# NAND-7S.net
KiCad netlist of a schematic drawn in EasyEDA Pro
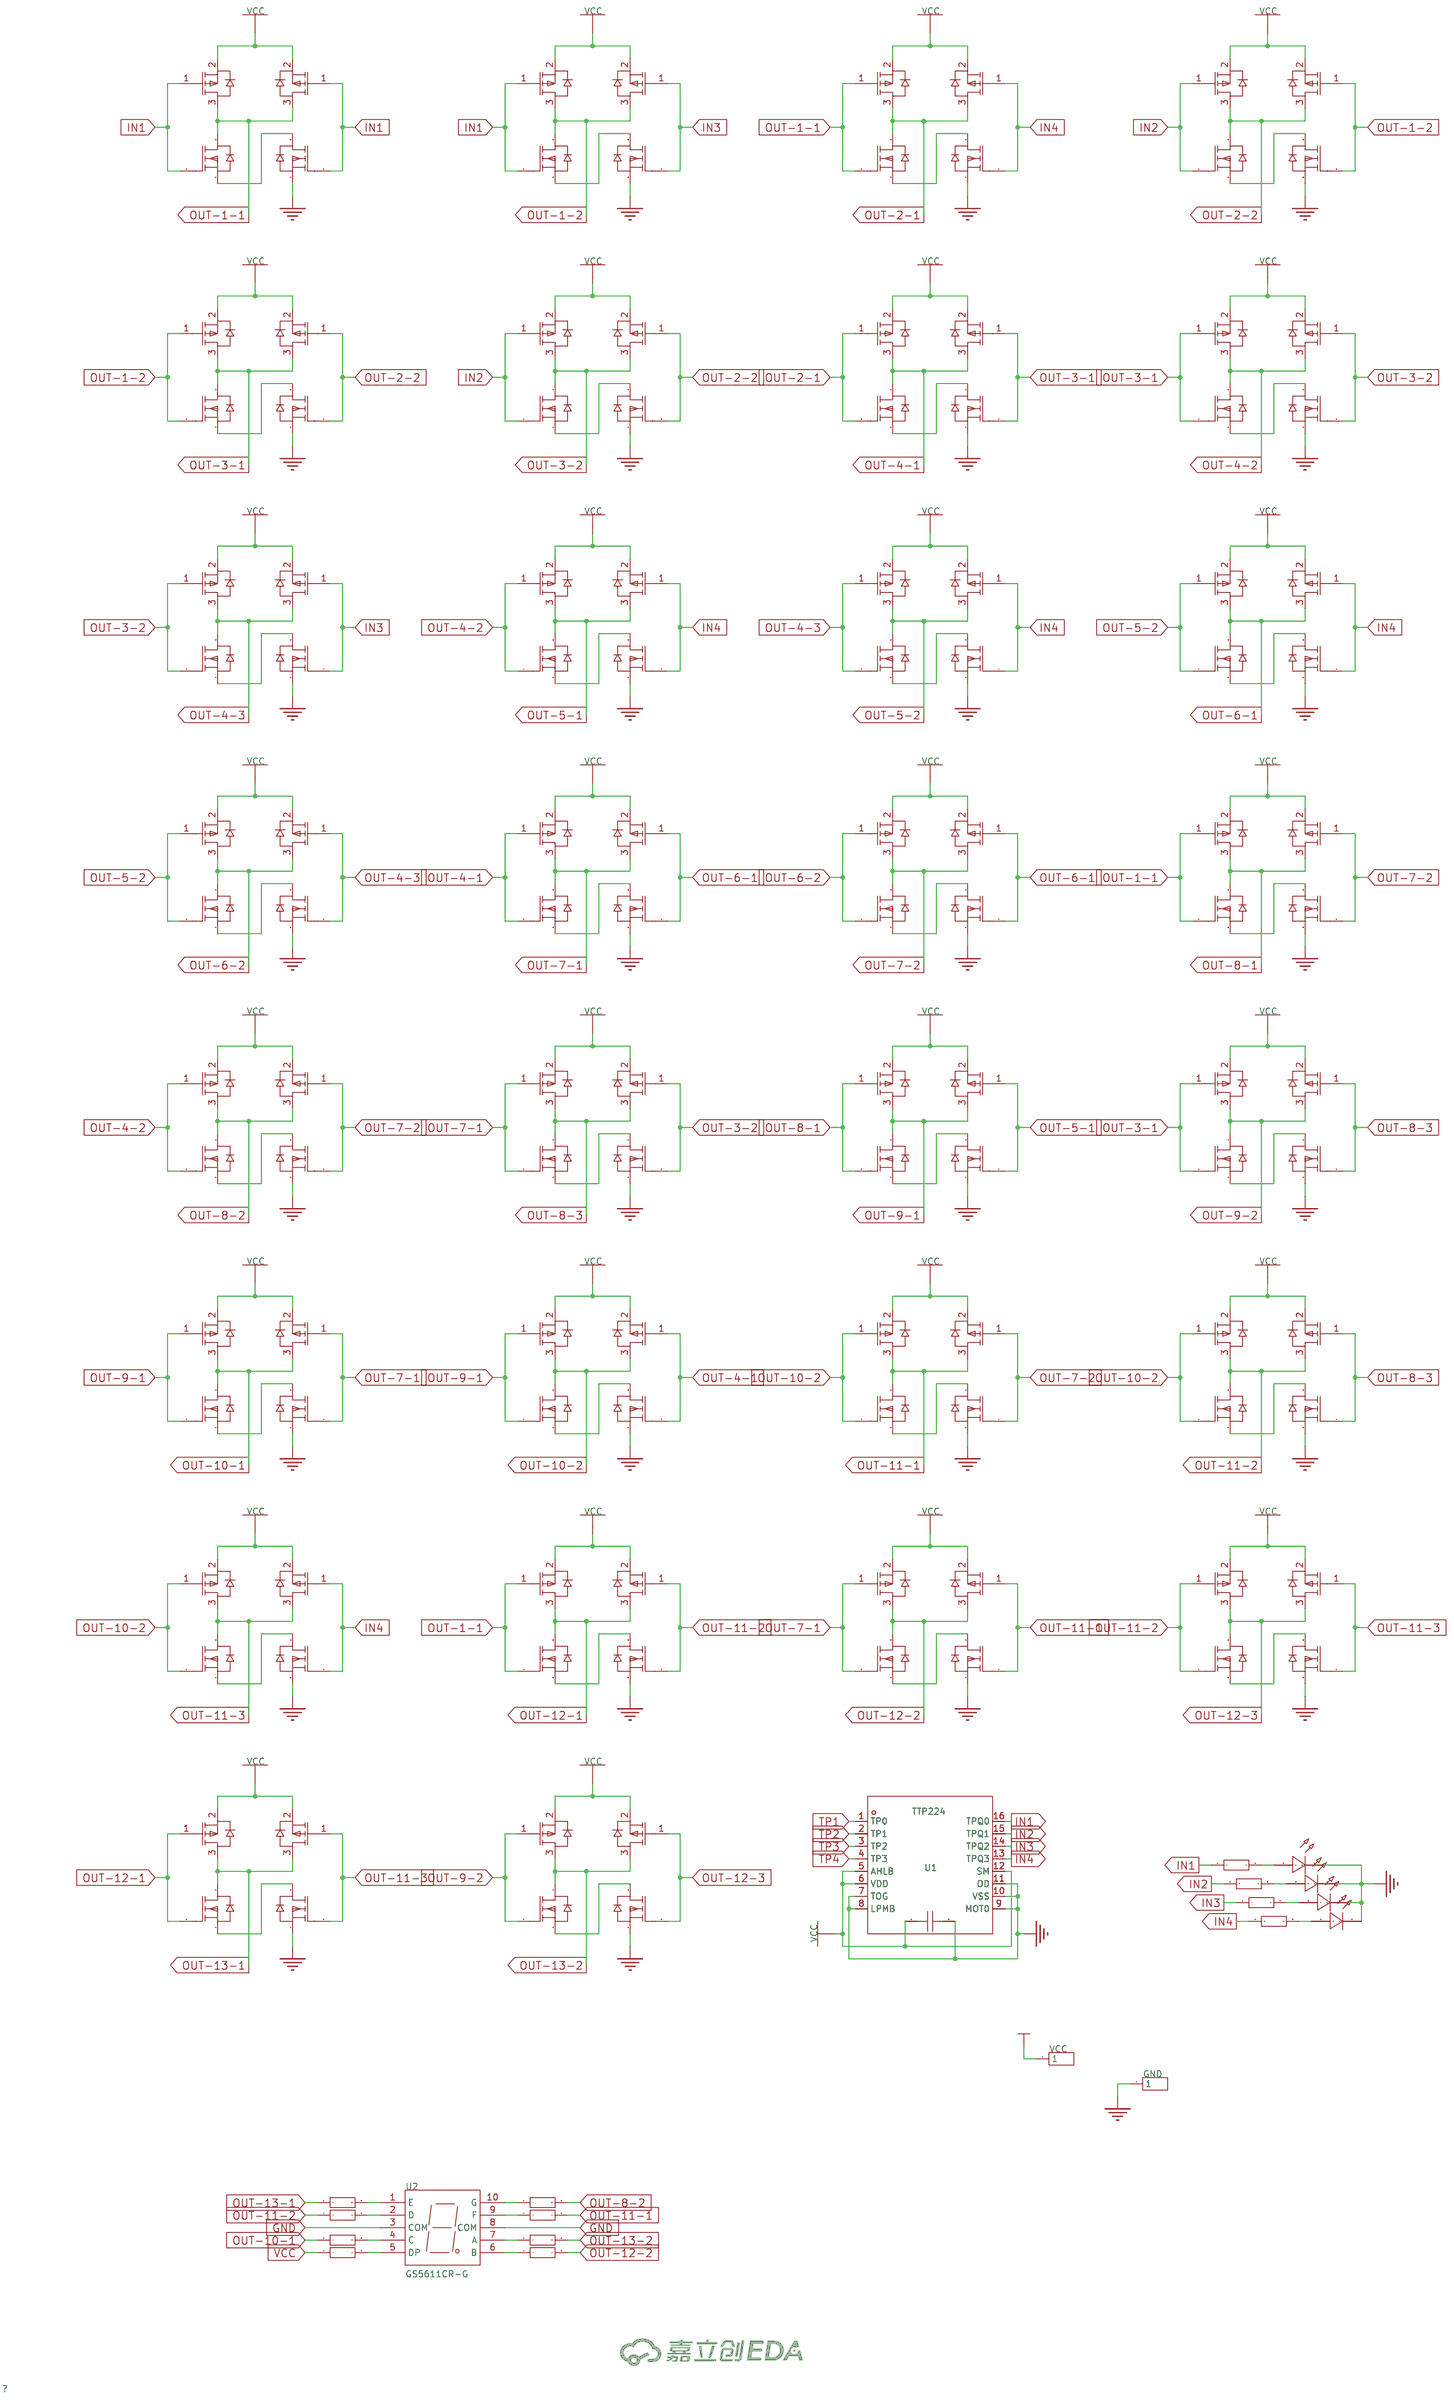
[diagram p0: schematic sheet]

(export (version "E")
  (design (tool "Eeschema 10.0.6"))
  (components
    (comp (ref "C1")
      (value "100nF")
      (footprint "easyedapro:C0603")
      (libsource (lib "easyedapro") (part "Capacitance"))
    )
    (comp (ref "GND")
      (value "GND")
      (footprint "easyedapro:HDR-TH_1P-V-M_XKB_X4611WV-01I-C28D40")
      (libsource (lib "easyedapro") (part "HDR_1x1"))
    )
    (comp (ref "LED1")
      (value "~")
      (footprint "easyedapro:LED_0603")
      (libsource (lib "easyedapro") (part "LED_R"))
    )
    (comp (ref "LED2")
      (value "~")
      (footprint "easyedapro:LED_0603")
      (libsource (lib "easyedapro") (part "LED_R"))
    )
    (comp (ref "LED3")
      (value "~")
      (footprint "easyedapro:LED_0603")
      (libsource (lib "easyedapro") (part "LED_R"))
    )
    (comp (ref "LED4")
      (value "~")
      (footprint "easyedapro:LED_0603")
      (libsource (lib "easyedapro") (part "LED_R"))
    )
    (comp (ref "N1-1")
      (value "CJ2304")
      (footprint "easyedapro:SOT-23_L2.9-W1.3-P1.90-LS2.4-BR")
      (fields (field (name "Manufacturer") "CJ（江苏长电/长晶）"))
      (libsource (lib "easyedapro") (part "2N7002LT1G"))
    )
    (comp (ref "N1-2")
      (value "CJ2304")
      (footprint "easyedapro:SOT-23_L2.9-W1.3-P1.90-LS2.4-BR")
      (fields (field (name "Manufacturer") "CJ（江苏长电/长晶）"))
      (libsource (lib "easyedapro") (part "2N7002LT1G"))
    )
    (comp (ref "N2-1")
      (value "CJ2304")
      (footprint "easyedapro:SOT-23_L2.9-W1.3-P1.90-LS2.4-BR")
      (fields (field (name "Manufacturer") "CJ（江苏长电/长晶）"))
      (libsource (lib "easyedapro") (part "2N7002LT1G"))
    )
    (comp (ref "N2-2")
      (value "CJ2304")
      (footprint "easyedapro:SOT-23_L2.9-W1.3-P1.90-LS2.4-BR")
      (fields (field (name "Manufacturer") "CJ（江苏长电/长晶）"))
      (libsource (lib "easyedapro") (part "2N7002LT1G"))
    )
    (comp (ref "N3-1")
      (value "CJ2304")
      (footprint "easyedapro:SOT-23_L2.9-W1.3-P1.90-LS2.4-BR")
      (fields (field (name "Manufacturer") "CJ（江苏长电/长晶）"))
      (libsource (lib "easyedapro") (part "2N7002LT1G"))
    )
    (comp (ref "N3-2")
      (value "CJ2304")
      (footprint "easyedapro:SOT-23_L2.9-W1.3-P1.90-LS2.4-BR")
      (fields (field (name "Manufacturer") "CJ（江苏长电/长晶）"))
      (libsource (lib "easyedapro") (part "2N7002LT1G"))
    )
    (comp (ref "N4-1")
      (value "CJ2304")
      (footprint "easyedapro:SOT-23_L2.9-W1.3-P1.90-LS2.4-BR")
      (fields (field (name "Manufacturer") "CJ（江苏长电/长晶）"))
      (libsource (lib "easyedapro") (part "2N7002LT1G"))
    )
    (comp (ref "N4-2")
      (value "CJ2304")
      (footprint "easyedapro:SOT-23_L2.9-W1.3-P1.90-LS2.4-BR")
      (fields (field (name "Manufacturer") "CJ（江苏长电/长晶）"))
      (libsource (lib "easyedapro") (part "2N7002LT1G"))
    )
    (comp (ref "N5-1")
      (value "CJ2304")
      (footprint "easyedapro:SOT-23_L2.9-W1.3-P1.90-LS2.4-BR")
      (fields (field (name "Manufacturer") "CJ（江苏长电/长晶）"))
      (libsource (lib "easyedapro") (part "2N7002LT1G"))
    )
    (comp (ref "N5-2")
      (value "CJ2304")
      (footprint "easyedapro:SOT-23_L2.9-W1.3-P1.90-LS2.4-BR")
      (fields (field (name "Manufacturer") "CJ（江苏长电/长晶）"))
      (libsource (lib "easyedapro") (part "2N7002LT1G"))
    )
    (comp (ref "N6-1")
      (value "CJ2304")
      (footprint "easyedapro:SOT-23_L2.9-W1.3-P1.90-LS2.4-BR")
      (fields (field (name "Manufacturer") "CJ（江苏长电/长晶）"))
      (libsource (lib "easyedapro") (part "2N7002LT1G"))
    )
    (comp (ref "N6-2")
      (value "CJ2304")
      (footprint "easyedapro:SOT-23_L2.9-W1.3-P1.90-LS2.4-BR")
      (fields (field (name "Manufacturer") "CJ（江苏长电/长晶）"))
      (libsource (lib "easyedapro") (part "2N7002LT1G"))
    )
    (comp (ref "N7-1")
      (value "CJ2304")
      (footprint "easyedapro:SOT-23_L2.9-W1.3-P1.90-LS2.4-BR")
      (fields (field (name "Manufacturer") "CJ（江苏长电/长晶）"))
      (libsource (lib "easyedapro") (part "2N7002LT1G"))
    )
    (comp (ref "N7-2")
      (value "CJ2304")
      (footprint "easyedapro:SOT-23_L2.9-W1.3-P1.90-LS2.4-BR")
      (fields (field (name "Manufacturer") "CJ（江苏长电/长晶）"))
      (libsource (lib "easyedapro") (part "2N7002LT1G"))
    )
    (comp (ref "N8-1")
      (value "CJ2304")
      (footprint "easyedapro:SOT-23_L2.9-W1.3-P1.90-LS2.4-BR")
      (fields (field (name "Manufacturer") "CJ（江苏长电/长晶）"))
      (libsource (lib "easyedapro") (part "2N7002LT1G"))
    )
    (comp (ref "N8-2")
      (value "CJ2304")
      (footprint "easyedapro:SOT-23_L2.9-W1.3-P1.90-LS2.4-BR")
      (fields (field (name "Manufacturer") "CJ（江苏长电/长晶）"))
      (libsource (lib "easyedapro") (part "2N7002LT1G"))
    )
    (comp (ref "N9-1")
      (value "CJ2304")
      (footprint "easyedapro:SOT-23_L2.9-W1.3-P1.90-LS2.4-BR")
      (fields (field (name "Manufacturer") "CJ（江苏长电/长晶）"))
      (libsource (lib "easyedapro") (part "2N7002LT1G"))
    )
    (comp (ref "N9-2")
      (value "CJ2304")
      (footprint "easyedapro:SOT-23_L2.9-W1.3-P1.90-LS2.4-BR")
      (fields (field (name "Manufacturer") "CJ（江苏长电/长晶）"))
      (libsource (lib "easyedapro") (part "2N7002LT1G"))
    )
    (comp (ref "N10-1")
      (value "CJ2304")
      (footprint "easyedapro:SOT-23_L2.9-W1.3-P1.90-LS2.4-BR")
      (fields (field (name "Manufacturer") "CJ（江苏长电/长晶）"))
      (libsource (lib "easyedapro") (part "2N7002LT1G"))
    )
    (comp (ref "N10-2")
      (value "CJ2304")
      (footprint "easyedapro:SOT-23_L2.9-W1.3-P1.90-LS2.4-BR")
      (fields (field (name "Manufacturer") "CJ（江苏长电/长晶）"))
      (libsource (lib "easyedapro") (part "2N7002LT1G"))
    )
    (comp (ref "N11-1")
      (value "CJ2304")
      (footprint "easyedapro:SOT-23_L2.9-W1.3-P1.90-LS2.4-BR")
      (fields (field (name "Manufacturer") "CJ（江苏长电/长晶）"))
      (libsource (lib "easyedapro") (part "2N7002LT1G"))
    )
    (comp (ref "N11-2")
      (value "CJ2304")
      (footprint "easyedapro:SOT-23_L2.9-W1.3-P1.90-LS2.4-BR")
      (fields (field (name "Manufacturer") "CJ（江苏长电/长晶）"))
      (libsource (lib "easyedapro") (part "2N7002LT1G"))
    )
    (comp (ref "N12-1")
      (value "CJ2304")
      (footprint "easyedapro:SOT-23_L2.9-W1.3-P1.90-LS2.4-BR")
      (fields (field (name "Manufacturer") "CJ（江苏长电/长晶）"))
      (libsource (lib "easyedapro") (part "2N7002LT1G"))
    )
    (comp (ref "N12-2")
      (value "CJ2304")
      (footprint "easyedapro:SOT-23_L2.9-W1.3-P1.90-LS2.4-BR")
      (fields (field (name "Manufacturer") "CJ（江苏长电/长晶）"))
      (libsource (lib "easyedapro") (part "2N7002LT1G"))
    )
    (comp (ref "N13-1")
      (value "CJ2304")
      (footprint "easyedapro:SOT-23_L2.9-W1.3-P1.90-LS2.4-BR")
      (fields (field (name "Manufacturer") "CJ（江苏长电/长晶）"))
      (libsource (lib "easyedapro") (part "2N7002LT1G"))
    )
    (comp (ref "N13-2")
      (value "CJ2304")
      (footprint "easyedapro:SOT-23_L2.9-W1.3-P1.90-LS2.4-BR")
      (fields (field (name "Manufacturer") "CJ（江苏长电/长晶）"))
      (libsource (lib "easyedapro") (part "2N7002LT1G"))
    )
    (comp (ref "N14-1")
      (value "CJ2304")
      (footprint "easyedapro:SOT-23_L2.9-W1.3-P1.90-LS2.4-BR")
      (fields (field (name "Manufacturer") "CJ（江苏长电/长晶）"))
      (libsource (lib "easyedapro") (part "2N7002LT1G"))
    )
    (comp (ref "N14-2")
      (value "CJ2304")
      (footprint "easyedapro:SOT-23_L2.9-W1.3-P1.90-LS2.4-BR")
      (fields (field (name "Manufacturer") "CJ（江苏长电/长晶）"))
      (libsource (lib "easyedapro") (part "2N7002LT1G"))
    )
    (comp (ref "N15-1")
      (value "CJ2304")
      (footprint "easyedapro:SOT-23_L2.9-W1.3-P1.90-LS2.4-BR")
      (fields (field (name "Manufacturer") "CJ（江苏长电/长晶）"))
      (libsource (lib "easyedapro") (part "2N7002LT1G"))
    )
    (comp (ref "N15-2")
      (value "CJ2304")
      (footprint "easyedapro:SOT-23_L2.9-W1.3-P1.90-LS2.4-BR")
      (fields (field (name "Manufacturer") "CJ（江苏长电/长晶）"))
      (libsource (lib "easyedapro") (part "2N7002LT1G"))
    )
    (comp (ref "N16-1")
      (value "CJ2304")
      (footprint "easyedapro:SOT-23_L2.9-W1.3-P1.90-LS2.4-BR")
      (fields (field (name "Manufacturer") "CJ（江苏长电/长晶）"))
      (libsource (lib "easyedapro") (part "2N7002LT1G"))
    )
    (comp (ref "N16-2")
      (value "CJ2304")
      (footprint "easyedapro:SOT-23_L2.9-W1.3-P1.90-LS2.4-BR")
      (fields (field (name "Manufacturer") "CJ（江苏长电/长晶）"))
      (libsource (lib "easyedapro") (part "2N7002LT1G"))
    )
    (comp (ref "N17-1")
      (value "CJ2304")
      (footprint "easyedapro:SOT-23_L2.9-W1.3-P1.90-LS2.4-BR")
      (fields (field (name "Manufacturer") "CJ（江苏长电/长晶）"))
      (libsource (lib "easyedapro") (part "2N7002LT1G"))
    )
    (comp (ref "N17-2")
      (value "CJ2304")
      (footprint "easyedapro:SOT-23_L2.9-W1.3-P1.90-LS2.4-BR")
      (fields (field (name "Manufacturer") "CJ（江苏长电/长晶）"))
      (libsource (lib "easyedapro") (part "2N7002LT1G"))
    )
    (comp (ref "N18-1")
      (value "CJ2304")
      (footprint "easyedapro:SOT-23_L2.9-W1.3-P1.90-LS2.4-BR")
      (fields (field (name "Manufacturer") "CJ（江苏长电/长晶）"))
      (libsource (lib "easyedapro") (part "2N7002LT1G"))
    )
    (comp (ref "N18-2")
      (value "CJ2304")
      (footprint "easyedapro:SOT-23_L2.9-W1.3-P1.90-LS2.4-BR")
      (fields (field (name "Manufacturer") "CJ（江苏长电/长晶）"))
      (libsource (lib "easyedapro") (part "2N7002LT1G"))
    )
    (comp (ref "N19-1")
      (value "CJ2304")
      (footprint "easyedapro:SOT-23_L2.9-W1.3-P1.90-LS2.4-BR")
      (fields (field (name "Manufacturer") "CJ（江苏长电/长晶）"))
      (libsource (lib "easyedapro") (part "2N7002LT1G"))
    )
    (comp (ref "N19-2")
      (value "CJ2304")
      (footprint "easyedapro:SOT-23_L2.9-W1.3-P1.90-LS2.4-BR")
      (fields (field (name "Manufacturer") "CJ（江苏长电/长晶）"))
      (libsource (lib "easyedapro") (part "2N7002LT1G"))
    )
    (comp (ref "N20-1")
      (value "CJ2304")
      (footprint "easyedapro:SOT-23_L2.9-W1.3-P1.90-LS2.4-BR")
      (fields (field (name "Manufacturer") "CJ（江苏长电/长晶）"))
      (libsource (lib "easyedapro") (part "2N7002LT1G"))
    )
    (comp (ref "N20-2")
      (value "CJ2304")
      (footprint "easyedapro:SOT-23_L2.9-W1.3-P1.90-LS2.4-BR")
      (fields (field (name "Manufacturer") "CJ（江苏长电/长晶）"))
      (libsource (lib "easyedapro") (part "2N7002LT1G"))
    )
    (comp (ref "N21-1")
      (value "CJ2304")
      (footprint "easyedapro:SOT-23_L2.9-W1.3-P1.90-LS2.4-BR")
      (fields (field (name "Manufacturer") "CJ（江苏长电/长晶）"))
      (libsource (lib "easyedapro") (part "2N7002LT1G"))
    )
    (comp (ref "N21-2")
      (value "CJ2304")
      (footprint "easyedapro:SOT-23_L2.9-W1.3-P1.90-LS2.4-BR")
      (fields (field (name "Manufacturer") "CJ（江苏长电/长晶）"))
      (libsource (lib "easyedapro") (part "2N7002LT1G"))
    )
    (comp (ref "N22-1")
      (value "CJ2304")
      (footprint "easyedapro:SOT-23_L2.9-W1.3-P1.90-LS2.4-BR")
      (fields (field (name "Manufacturer") "CJ（江苏长电/长晶）"))
      (libsource (lib "easyedapro") (part "2N7002LT1G"))
    )
    (comp (ref "N22-2")
      (value "CJ2304")
      (footprint "easyedapro:SOT-23_L2.9-W1.3-P1.90-LS2.4-BR")
      (fields (field (name "Manufacturer") "CJ（江苏长电/长晶）"))
      (libsource (lib "easyedapro") (part "2N7002LT1G"))
    )
    (comp (ref "N23-1")
      (value "CJ2304")
      (footprint "easyedapro:SOT-23_L2.9-W1.3-P1.90-LS2.4-BR")
      (fields (field (name "Manufacturer") "CJ（江苏长电/长晶）"))
      (libsource (lib "easyedapro") (part "2N7002LT1G"))
    )
    (comp (ref "N23-2")
      (value "CJ2304")
      (footprint "easyedapro:SOT-23_L2.9-W1.3-P1.90-LS2.4-BR")
      (fields (field (name "Manufacturer") "CJ（江苏长电/长晶）"))
      (libsource (lib "easyedapro") (part "2N7002LT1G"))
    )
    (comp (ref "N24-1")
      (value "CJ2304")
      (footprint "easyedapro:SOT-23_L2.9-W1.3-P1.90-LS2.4-BR")
      (fields (field (name "Manufacturer") "CJ（江苏长电/长晶）"))
      (libsource (lib "easyedapro") (part "2N7002LT1G"))
    )
    (comp (ref "N24-2")
      (value "CJ2304")
      (footprint "easyedapro:SOT-23_L2.9-W1.3-P1.90-LS2.4-BR")
      (fields (field (name "Manufacturer") "CJ（江苏长电/长晶）"))
      (libsource (lib "easyedapro") (part "2N7002LT1G"))
    )
    (comp (ref "N25-1")
      (value "CJ2304")
      (footprint "easyedapro:SOT-23_L2.9-W1.3-P1.90-LS2.4-BR")
      (fields (field (name "Manufacturer") "CJ（江苏长电/长晶）"))
      (libsource (lib "easyedapro") (part "2N7002LT1G"))
    )
    (comp (ref "N25-2")
      (value "CJ2304")
      (footprint "easyedapro:SOT-23_L2.9-W1.3-P1.90-LS2.4-BR")
      (fields (field (name "Manufacturer") "CJ（江苏长电/长晶）"))
      (libsource (lib "easyedapro") (part "2N7002LT1G"))
    )
    (comp (ref "N26-1")
      (value "CJ2304")
      (footprint "easyedapro:SOT-23_L2.9-W1.3-P1.90-LS2.4-BR")
      (fields (field (name "Manufacturer") "CJ（江苏长电/长晶）"))
      (libsource (lib "easyedapro") (part "2N7002LT1G"))
    )
    (comp (ref "N26-2")
      (value "CJ2304")
      (footprint "easyedapro:SOT-23_L2.9-W1.3-P1.90-LS2.4-BR")
      (fields (field (name "Manufacturer") "CJ（江苏长电/长晶）"))
      (libsource (lib "easyedapro") (part "2N7002LT1G"))
    )
    (comp (ref "N27-1")
      (value "CJ2304")
      (footprint "easyedapro:SOT-23_L2.9-W1.3-P1.90-LS2.4-BR")
      (fields (field (name "Manufacturer") "CJ（江苏长电/长晶）"))
      (libsource (lib "easyedapro") (part "2N7002LT1G"))
    )
    (comp (ref "N27-2")
      (value "CJ2304")
      (footprint "easyedapro:SOT-23_L2.9-W1.3-P1.90-LS2.4-BR")
      (fields (field (name "Manufacturer") "CJ（江苏长电/长晶）"))
      (libsource (lib "easyedapro") (part "2N7002LT1G"))
    )
    (comp (ref "N28-1")
      (value "CJ2304")
      (footprint "easyedapro:SOT-23_L2.9-W1.3-P1.90-LS2.4-BR")
      (fields (field (name "Manufacturer") "CJ（江苏长电/长晶）"))
      (libsource (lib "easyedapro") (part "2N7002LT1G"))
    )
    (comp (ref "N28-2")
      (value "CJ2304")
      (footprint "easyedapro:SOT-23_L2.9-W1.3-P1.90-LS2.4-BR")
      (fields (field (name "Manufacturer") "CJ（江苏长电/长晶）"))
      (libsource (lib "easyedapro") (part "2N7002LT1G"))
    )
    (comp (ref "N29-1")
      (value "CJ2304")
      (footprint "easyedapro:SOT-23_L2.9-W1.3-P1.90-LS2.4-BR")
      (fields (field (name "Manufacturer") "CJ（江苏长电/长晶）"))
      (libsource (lib "easyedapro") (part "2N7002LT1G"))
    )
    (comp (ref "N29-2")
      (value "CJ2304")
      (footprint "easyedapro:SOT-23_L2.9-W1.3-P1.90-LS2.4-BR")
      (fields (field (name "Manufacturer") "CJ（江苏长电/长晶）"))
      (libsource (lib "easyedapro") (part "2N7002LT1G"))
    )
    (comp (ref "N30-1")
      (value "CJ2304")
      (footprint "easyedapro:SOT-23_L2.9-W1.3-P1.90-LS2.4-BR")
      (fields (field (name "Manufacturer") "CJ（江苏长电/长晶）"))
      (libsource (lib "easyedapro") (part "2N7002LT1G"))
    )
    (comp (ref "N30-2")
      (value "CJ2304")
      (footprint "easyedapro:SOT-23_L2.9-W1.3-P1.90-LS2.4-BR")
      (fields (field (name "Manufacturer") "CJ（江苏长电/长晶）"))
      (libsource (lib "easyedapro") (part "2N7002LT1G"))
    )
    (comp (ref "P1-1")
      (value "LP2301LT1G")
      (footprint "easyedapro:SOT-23-3_L2.9-W1.3-P1.90-LS2.4-TR-1")
      (fields (field (name "Manufacturer") "LRC(乐山无线电)"))
      (libsource (lib "easyedapro") (part "SI2301_C351397"))
    )
    (comp (ref "P1-2")
      (value "LP2301LT1G")
      (footprint "easyedapro:SOT-23-3_L2.9-W1.3-P1.90-LS2.4-TR-1")
      (fields (field (name "Manufacturer") "LRC(乐山无线电)"))
      (libsource (lib "easyedapro") (part "SI2301_C351397"))
    )
    (comp (ref "P2-1")
      (value "LP2301LT1G")
      (footprint "easyedapro:SOT-23-3_L2.9-W1.3-P1.90-LS2.4-TR-1")
      (fields (field (name "Manufacturer") "LRC(乐山无线电)"))
      (libsource (lib "easyedapro") (part "SI2301_C351397"))
    )
    (comp (ref "P2-2")
      (value "LP2301LT1G")
      (footprint "easyedapro:SOT-23-3_L2.9-W1.3-P1.90-LS2.4-TR-1")
      (fields (field (name "Manufacturer") "LRC(乐山无线电)"))
      (libsource (lib "easyedapro") (part "SI2301_C351397"))
    )
    (comp (ref "P3-1")
      (value "LP2301LT1G")
      (footprint "easyedapro:SOT-23-3_L2.9-W1.3-P1.90-LS2.4-TR-1")
      (fields (field (name "Manufacturer") "LRC(乐山无线电)"))
      (libsource (lib "easyedapro") (part "SI2301_C351397"))
    )
    (comp (ref "P3-2")
      (value "LP2301LT1G")
      (footprint "easyedapro:SOT-23-3_L2.9-W1.3-P1.90-LS2.4-TR-1")
      (fields (field (name "Manufacturer") "LRC(乐山无线电)"))
      (libsource (lib "easyedapro") (part "SI2301_C351397"))
    )
    (comp (ref "P4-1")
      (value "LP2301LT1G")
      (footprint "easyedapro:SOT-23-3_L2.9-W1.3-P1.90-LS2.4-TR-1")
      (fields (field (name "Manufacturer") "LRC(乐山无线电)"))
      (libsource (lib "easyedapro") (part "SI2301_C351397"))
    )
    (comp (ref "P4-2")
      (value "LP2301LT1G")
      (footprint "easyedapro:SOT-23-3_L2.9-W1.3-P1.90-LS2.4-TR-1")
      (fields (field (name "Manufacturer") "LRC(乐山无线电)"))
      (libsource (lib "easyedapro") (part "SI2301_C351397"))
    )
    (comp (ref "P5-1")
      (value "LP2301LT1G")
      (footprint "easyedapro:SOT-23-3_L2.9-W1.3-P1.90-LS2.4-TR-1")
      (fields (field (name "Manufacturer") "LRC(乐山无线电)"))
      (libsource (lib "easyedapro") (part "SI2301_C351397"))
    )
    (comp (ref "P5-2")
      (value "LP2301LT1G")
      (footprint "easyedapro:SOT-23-3_L2.9-W1.3-P1.90-LS2.4-TR-1")
      (fields (field (name "Manufacturer") "LRC(乐山无线电)"))
      (libsource (lib "easyedapro") (part "SI2301_C351397"))
    )
    (comp (ref "P6-1")
      (value "LP2301LT1G")
      (footprint "easyedapro:SOT-23-3_L2.9-W1.3-P1.90-LS2.4-TR-1")
      (fields (field (name "Manufacturer") "LRC(乐山无线电)"))
      (libsource (lib "easyedapro") (part "SI2301_C351397"))
    )
    (comp (ref "P6-2")
      (value "LP2301LT1G")
      (footprint "easyedapro:SOT-23-3_L2.9-W1.3-P1.90-LS2.4-TR-1")
      (fields (field (name "Manufacturer") "LRC(乐山无线电)"))
      (libsource (lib "easyedapro") (part "SI2301_C351397"))
    )
    (comp (ref "P7-1")
      (value "LP2301LT1G")
      (footprint "easyedapro:SOT-23-3_L2.9-W1.3-P1.90-LS2.4-TR-1")
      (fields (field (name "Manufacturer") "LRC(乐山无线电)"))
      (libsource (lib "easyedapro") (part "SI2301_C351397"))
    )
    (comp (ref "P7-2")
      (value "LP2301LT1G")
      (footprint "easyedapro:SOT-23-3_L2.9-W1.3-P1.90-LS2.4-TR-1")
      (fields (field (name "Manufacturer") "LRC(乐山无线电)"))
      (libsource (lib "easyedapro") (part "SI2301_C351397"))
    )
    (comp (ref "P8-1")
      (value "LP2301LT1G")
      (footprint "easyedapro:SOT-23-3_L2.9-W1.3-P1.90-LS2.4-TR-1")
      (fields (field (name "Manufacturer") "LRC(乐山无线电)"))
      (libsource (lib "easyedapro") (part "SI2301_C351397"))
    )
    (comp (ref "P8-2")
      (value "LP2301LT1G")
      (footprint "easyedapro:SOT-23-3_L2.9-W1.3-P1.90-LS2.4-TR-1")
      (fields (field (name "Manufacturer") "LRC(乐山无线电)"))
      (libsource (lib "easyedapro") (part "SI2301_C351397"))
    )
    (comp (ref "P9-1")
      (value "LP2301LT1G")
      (footprint "easyedapro:SOT-23-3_L2.9-W1.3-P1.90-LS2.4-TR-1")
      (fields (field (name "Manufacturer") "LRC(乐山无线电)"))
      (libsource (lib "easyedapro") (part "SI2301_C351397"))
    )
    (comp (ref "P9-2")
      (value "LP2301LT1G")
      (footprint "easyedapro:SOT-23-3_L2.9-W1.3-P1.90-LS2.4-TR-1")
      (fields (field (name "Manufacturer") "LRC(乐山无线电)"))
      (libsource (lib "easyedapro") (part "SI2301_C351397"))
    )
    (comp (ref "P10-1")
      (value "LP2301LT1G")
      (footprint "easyedapro:SOT-23-3_L2.9-W1.3-P1.90-LS2.4-TR-1")
      (fields (field (name "Manufacturer") "LRC(乐山无线电)"))
      (libsource (lib "easyedapro") (part "SI2301_C351397"))
    )
    (comp (ref "P10-2")
      (value "LP2301LT1G")
      (footprint "easyedapro:SOT-23-3_L2.9-W1.3-P1.90-LS2.4-TR-1")
      (fields (field (name "Manufacturer") "LRC(乐山无线电)"))
      (libsource (lib "easyedapro") (part "SI2301_C351397"))
    )
    (comp (ref "P11-1")
      (value "LP2301LT1G")
      (footprint "easyedapro:SOT-23-3_L2.9-W1.3-P1.90-LS2.4-TR-1")
      (fields (field (name "Manufacturer") "LRC(乐山无线电)"))
      (libsource (lib "easyedapro") (part "SI2301_C351397"))
    )
    (comp (ref "P11-2")
      (value "LP2301LT1G")
      (footprint "easyedapro:SOT-23-3_L2.9-W1.3-P1.90-LS2.4-TR-1")
      (fields (field (name "Manufacturer") "LRC(乐山无线电)"))
      (libsource (lib "easyedapro") (part "SI2301_C351397"))
    )
    (comp (ref "P12-1")
      (value "LP2301LT1G")
      (footprint "easyedapro:SOT-23-3_L2.9-W1.3-P1.90-LS2.4-TR-1")
      (fields (field (name "Manufacturer") "LRC(乐山无线电)"))
      (libsource (lib "easyedapro") (part "SI2301_C351397"))
    )
    (comp (ref "P12-2")
      (value "LP2301LT1G")
      (footprint "easyedapro:SOT-23-3_L2.9-W1.3-P1.90-LS2.4-TR-1")
      (fields (field (name "Manufacturer") "LRC(乐山无线电)"))
      (libsource (lib "easyedapro") (part "SI2301_C351397"))
    )
    (comp (ref "P13-1")
      (value "LP2301LT1G")
      (footprint "easyedapro:SOT-23-3_L2.9-W1.3-P1.90-LS2.4-TR-1")
      (fields (field (name "Manufacturer") "LRC(乐山无线电)"))
      (libsource (lib "easyedapro") (part "SI2301_C351397"))
    )
    (comp (ref "P13-2")
      (value "LP2301LT1G")
      (footprint "easyedapro:SOT-23-3_L2.9-W1.3-P1.90-LS2.4-TR-1")
      (fields (field (name "Manufacturer") "LRC(乐山无线电)"))
      (libsource (lib "easyedapro") (part "SI2301_C351397"))
    )
    (comp (ref "P14-1")
      (value "LP2301LT1G")
      (footprint "easyedapro:SOT-23-3_L2.9-W1.3-P1.90-LS2.4-TR-1")
      (fields (field (name "Manufacturer") "LRC(乐山无线电)"))
      (libsource (lib "easyedapro") (part "SI2301_C351397"))
    )
    (comp (ref "P14-2")
      (value "LP2301LT1G")
      (footprint "easyedapro:SOT-23-3_L2.9-W1.3-P1.90-LS2.4-TR-1")
      (fields (field (name "Manufacturer") "LRC(乐山无线电)"))
      (libsource (lib "easyedapro") (part "SI2301_C351397"))
    )
    (comp (ref "P15-1")
      (value "LP2301LT1G")
      (footprint "easyedapro:SOT-23-3_L2.9-W1.3-P1.90-LS2.4-TR-1")
      (fields (field (name "Manufacturer") "LRC(乐山无线电)"))
      (libsource (lib "easyedapro") (part "SI2301_C351397"))
    )
    (comp (ref "P15-2")
      (value "LP2301LT1G")
      (footprint "easyedapro:SOT-23-3_L2.9-W1.3-P1.90-LS2.4-TR-1")
      (fields (field (name "Manufacturer") "LRC(乐山无线电)"))
      (libsource (lib "easyedapro") (part "SI2301_C351397"))
    )
    (comp (ref "P16-1")
      (value "LP2301LT1G")
      (footprint "easyedapro:SOT-23-3_L2.9-W1.3-P1.90-LS2.4-TR-1")
      (fields (field (name "Manufacturer") "LRC(乐山无线电)"))
      (libsource (lib "easyedapro") (part "SI2301_C351397"))
    )
    (comp (ref "P16-2")
      (value "LP2301LT1G")
      (footprint "easyedapro:SOT-23-3_L2.9-W1.3-P1.90-LS2.4-TR-1")
      (fields (field (name "Manufacturer") "LRC(乐山无线电)"))
      (libsource (lib "easyedapro") (part "SI2301_C351397"))
    )
    (comp (ref "P17-1")
      (value "LP2301LT1G")
      (footprint "easyedapro:SOT-23-3_L2.9-W1.3-P1.90-LS2.4-TR-1")
      (fields (field (name "Manufacturer") "LRC(乐山无线电)"))
      (libsource (lib "easyedapro") (part "SI2301_C351397"))
    )
    (comp (ref "P17-2")
      (value "LP2301LT1G")
      (footprint "easyedapro:SOT-23-3_L2.9-W1.3-P1.90-LS2.4-TR-1")
      (fields (field (name "Manufacturer") "LRC(乐山无线电)"))
      (libsource (lib "easyedapro") (part "SI2301_C351397"))
    )
    (comp (ref "P18-1")
      (value "LP2301LT1G")
      (footprint "easyedapro:SOT-23-3_L2.9-W1.3-P1.90-LS2.4-TR-1")
      (fields (field (name "Manufacturer") "LRC(乐山无线电)"))
      (libsource (lib "easyedapro") (part "SI2301_C351397"))
    )
    (comp (ref "P18-2")
      (value "LP2301LT1G")
      (footprint "easyedapro:SOT-23-3_L2.9-W1.3-P1.90-LS2.4-TR-1")
      (fields (field (name "Manufacturer") "LRC(乐山无线电)"))
      (libsource (lib "easyedapro") (part "SI2301_C351397"))
    )
    (comp (ref "P19-1")
      (value "LP2301LT1G")
      (footprint "easyedapro:SOT-23-3_L2.9-W1.3-P1.90-LS2.4-TR-1")
      (fields (field (name "Manufacturer") "LRC(乐山无线电)"))
      (libsource (lib "easyedapro") (part "SI2301_C351397"))
    )
    (comp (ref "P19-2")
      (value "LP2301LT1G")
      (footprint "easyedapro:SOT-23-3_L2.9-W1.3-P1.90-LS2.4-TR-1")
      (fields (field (name "Manufacturer") "LRC(乐山无线电)"))
      (libsource (lib "easyedapro") (part "SI2301_C351397"))
    )
    (comp (ref "P20-1")
      (value "LP2301LT1G")
      (footprint "easyedapro:SOT-23-3_L2.9-W1.3-P1.90-LS2.4-TR-1")
      (fields (field (name "Manufacturer") "LRC(乐山无线电)"))
      (libsource (lib "easyedapro") (part "SI2301_C351397"))
    )
    (comp (ref "P20-2")
      (value "LP2301LT1G")
      (footprint "easyedapro:SOT-23-3_L2.9-W1.3-P1.90-LS2.4-TR-1")
      (fields (field (name "Manufacturer") "LRC(乐山无线电)"))
      (libsource (lib "easyedapro") (part "SI2301_C351397"))
    )
    (comp (ref "P21-1")
      (value "LP2301LT1G")
      (footprint "easyedapro:SOT-23-3_L2.9-W1.3-P1.90-LS2.4-TR-1")
      (fields (field (name "Manufacturer") "LRC(乐山无线电)"))
      (libsource (lib "easyedapro") (part "SI2301_C351397"))
    )
    (comp (ref "P21-2")
      (value "LP2301LT1G")
      (footprint "easyedapro:SOT-23-3_L2.9-W1.3-P1.90-LS2.4-TR-1")
      (fields (field (name "Manufacturer") "LRC(乐山无线电)"))
      (libsource (lib "easyedapro") (part "SI2301_C351397"))
    )
    (comp (ref "P22-1")
      (value "LP2301LT1G")
      (footprint "easyedapro:SOT-23-3_L2.9-W1.3-P1.90-LS2.4-TR-1")
      (fields (field (name "Manufacturer") "LRC(乐山无线电)"))
      (libsource (lib "easyedapro") (part "SI2301_C351397"))
    )
    (comp (ref "P22-2")
      (value "LP2301LT1G")
      (footprint "easyedapro:SOT-23-3_L2.9-W1.3-P1.90-LS2.4-TR-1")
      (fields (field (name "Manufacturer") "LRC(乐山无线电)"))
      (libsource (lib "easyedapro") (part "SI2301_C351397"))
    )
    (comp (ref "P23-1")
      (value "LP2301LT1G")
      (footprint "easyedapro:SOT-23-3_L2.9-W1.3-P1.90-LS2.4-TR-1")
      (fields (field (name "Manufacturer") "LRC(乐山无线电)"))
      (libsource (lib "easyedapro") (part "SI2301_C351397"))
    )
    (comp (ref "P23-2")
      (value "LP2301LT1G")
      (footprint "easyedapro:SOT-23-3_L2.9-W1.3-P1.90-LS2.4-TR-1")
      (fields (field (name "Manufacturer") "LRC(乐山无线电)"))
      (libsource (lib "easyedapro") (part "SI2301_C351397"))
    )
    (comp (ref "P24-1")
      (value "LP2301LT1G")
      (footprint "easyedapro:SOT-23-3_L2.9-W1.3-P1.90-LS2.4-TR-1")
      (fields (field (name "Manufacturer") "LRC(乐山无线电)"))
      (libsource (lib "easyedapro") (part "SI2301_C351397"))
    )
    (comp (ref "P24-2")
      (value "LP2301LT1G")
      (footprint "easyedapro:SOT-23-3_L2.9-W1.3-P1.90-LS2.4-TR-1")
      (fields (field (name "Manufacturer") "LRC(乐山无线电)"))
      (libsource (lib "easyedapro") (part "SI2301_C351397"))
    )
    (comp (ref "P25-1")
      (value "LP2301LT1G")
      (footprint "easyedapro:SOT-23-3_L2.9-W1.3-P1.90-LS2.4-TR-1")
      (fields (field (name "Manufacturer") "LRC(乐山无线电)"))
      (libsource (lib "easyedapro") (part "SI2301_C351397"))
    )
    (comp (ref "P25-2")
      (value "LP2301LT1G")
      (footprint "easyedapro:SOT-23-3_L2.9-W1.3-P1.90-LS2.4-TR-1")
      (fields (field (name "Manufacturer") "LRC(乐山无线电)"))
      (libsource (lib "easyedapro") (part "SI2301_C351397"))
    )
    (comp (ref "P26-1")
      (value "LP2301LT1G")
      (footprint "easyedapro:SOT-23-3_L2.9-W1.3-P1.90-LS2.4-TR-1")
      (fields (field (name "Manufacturer") "LRC(乐山无线电)"))
      (libsource (lib "easyedapro") (part "SI2301_C351397"))
    )
    (comp (ref "P26-2")
      (value "LP2301LT1G")
      (footprint "easyedapro:SOT-23-3_L2.9-W1.3-P1.90-LS2.4-TR-1")
      (fields (field (name "Manufacturer") "LRC(乐山无线电)"))
      (libsource (lib "easyedapro") (part "SI2301_C351397"))
    )
    (comp (ref "P27-1")
      (value "LP2301LT1G")
      (footprint "easyedapro:SOT-23-3_L2.9-W1.3-P1.90-LS2.4-TR-1")
      (fields (field (name "Manufacturer") "LRC(乐山无线电)"))
      (libsource (lib "easyedapro") (part "SI2301_C351397"))
    )
    (comp (ref "P27-2")
      (value "LP2301LT1G")
      (footprint "easyedapro:SOT-23-3_L2.9-W1.3-P1.90-LS2.4-TR-1")
      (fields (field (name "Manufacturer") "LRC(乐山无线电)"))
      (libsource (lib "easyedapro") (part "SI2301_C351397"))
    )
    (comp (ref "P28-1")
      (value "LP2301LT1G")
      (footprint "easyedapro:SOT-23-3_L2.9-W1.3-P1.90-LS2.4-TR-1")
      (fields (field (name "Manufacturer") "LRC(乐山无线电)"))
      (libsource (lib "easyedapro") (part "SI2301_C351397"))
    )
    (comp (ref "P28-2")
      (value "LP2301LT1G")
      (footprint "easyedapro:SOT-23-3_L2.9-W1.3-P1.90-LS2.4-TR-1")
      (fields (field (name "Manufacturer") "LRC(乐山无线电)"))
      (libsource (lib "easyedapro") (part "SI2301_C351397"))
    )
    (comp (ref "P29-1")
      (value "LP2301LT1G")
      (footprint "easyedapro:SOT-23-3_L2.9-W1.3-P1.90-LS2.4-TR-1")
      (fields (field (name "Manufacturer") "LRC(乐山无线电)"))
      (libsource (lib "easyedapro") (part "SI2301_C351397"))
    )
    (comp (ref "P29-2")
      (value "LP2301LT1G")
      (footprint "easyedapro:SOT-23-3_L2.9-W1.3-P1.90-LS2.4-TR-1")
      (fields (field (name "Manufacturer") "LRC(乐山无线电)"))
      (libsource (lib "easyedapro") (part "SI2301_C351397"))
    )
    (comp (ref "P30-1")
      (value "LP2301LT1G")
      (footprint "easyedapro:SOT-23-3_L2.9-W1.3-P1.90-LS2.4-TR-1")
      (fields (field (name "Manufacturer") "LRC(乐山无线电)"))
      (libsource (lib "easyedapro") (part "SI2301_C351397"))
    )
    (comp (ref "P30-2")
      (value "LP2301LT1G")
      (footprint "easyedapro:SOT-23-3_L2.9-W1.3-P1.90-LS2.4-TR-1")
      (fields (field (name "Manufacturer") "LRC(乐山无线电)"))
      (libsource (lib "easyedapro") (part "SI2301_C351397"))
    )
    (comp (ref "R1") (value "470") (footprint "easyedapro:R0603") (libsource (lib "easyedapro") (part "电阻")))
    (comp (ref "R2") (value "470") (footprint "easyedapro:R0603") (libsource (lib "easyedapro") (part "电阻")))
    (comp (ref "R3") (value "470") (footprint "easyedapro:R0603") (libsource (lib "easyedapro") (part "电阻")))
    (comp (ref "R4") (value "470") (footprint "easyedapro:R0603") (libsource (lib "easyedapro") (part "电阻")))
    (comp (ref "R5") (value "470") (footprint "easyedapro:R0603") (libsource (lib "easyedapro") (part "电阻")))
    (comp (ref "R6") (value "470") (footprint "easyedapro:R0603") (libsource (lib "easyedapro") (part "电阻")))
    (comp (ref "R8") (value "470") (footprint "easyedapro:R0603") (libsource (lib "easyedapro") (part "电阻")))
    (comp (ref "R9") (value "470") (footprint "easyedapro:R0603") (libsource (lib "easyedapro") (part "电阻")))
    (comp (ref "R10") (value "470") (footprint "easyedapro:R0603") (libsource (lib "easyedapro") (part "电阻")))
    (comp (ref "R11") (value "470") (footprint "easyedapro:R0603") (libsource (lib "easyedapro") (part "电阻")))
    (comp (ref "R13") (value "470") (footprint "easyedapro:R0603") (libsource (lib "easyedapro") (part "电阻")))
    (comp (ref "R14") (value "470") (footprint "easyedapro:R0603") (libsource (lib "easyedapro") (part "电阻")))
    (comp (ref "U1")
      (value "TTP224")
      (footprint "easyedapro:TSSOP-16_L5.0-W4.4-P0.65-LS6.4-BL")
      (description "表面无字不接受投诉，4路触摸芯片，工作电流2.5uA，四路1对1方式输出，单独调灵敏度。直接替换老型号TTP224N-BSB（有丝印）")
      (fields (field (name "Manufacturer Part") "TTP224B-BSBN") (field (name "Manufacturer") "TONTEK(台湾通泰)"))
      (libsource (lib "easyedapro") (part "TTP224B-BSBN"))
    )
    (comp (ref "U2")
      (value "GS5611CR-G")
      (footprint "easyedapro:LED-SEG-SMD_GS5611CR-G")
      (description "0.56英寸，单八，共阴，红光，灰面贴片数码管")
      (fields (field (name "Manufacturer") "Guangcai Display(光彩显示)"))
      (libsource (lib "easyedapro") (part "GS5611CR-G"))
    )
    (comp (ref "VCC")
      (value "VCC")
      (footprint "easyedapro:HDR-TH_1P-V-M_XKB_X4611WV-01I-C28D40")
      (libsource (lib "easyedapro") (part "HDR_1x1"))
    )
  )
  (nets
    (net (code "1") (name "GND") (class "Default")
      (node (ref "C1") (pin "2") (pinfunction "2_2") (pintype "input"))
      (node (ref "GND") (pin "1") (pinfunction "1_1") (pintype "unspecified"))
      (node (ref "LED1") (pin "1") (pinfunction "C_1") (pintype "input"))
      (node (ref "LED2") (pin "1") (pinfunction "C_1") (pintype "input"))
      (node (ref "LED3") (pin "1") (pinfunction "C_1") (pintype "input"))
      (node (ref "LED4") (pin "1") (pinfunction "C_1") (pintype "input"))
      (node (ref "N1-2") (pin "2") (pinfunction "S_2") (pintype "input"))
      (node (ref "N10-2") (pin "2") (pinfunction "S_2") (pintype "input"))
      (node (ref "N11-2") (pin "2") (pinfunction "S_2") (pintype "input"))
      (node (ref "N12-2") (pin "2") (pinfunction "S_2") (pintype "input"))
      (node (ref "N13-2") (pin "2") (pinfunction "S_2") (pintype "input"))
      (node (ref "N14-2") (pin "2") (pinfunction "S_2") (pintype "input"))
      (node (ref "N15-2") (pin "2") (pinfunction "S_2") (pintype "input"))
      (node (ref "N16-2") (pin "2") (pinfunction "S_2") (pintype "input"))
      (node (ref "N17-2") (pin "2") (pinfunction "S_2") (pintype "input"))
      (node (ref "N18-2") (pin "2") (pinfunction "S_2") (pintype "input"))
      (node (ref "N19-2") (pin "2") (pinfunction "S_2") (pintype "input"))
      (node (ref "N2-2") (pin "2") (pinfunction "S_2") (pintype "input"))
      (node (ref "N20-2") (pin "2") (pinfunction "S_2") (pintype "input"))
      (node (ref "N21-2") (pin "2") (pinfunction "S_2") (pintype "input"))
      (node (ref "N22-2") (pin "2") (pinfunction "S_2") (pintype "input"))
      (node (ref "N23-2") (pin "2") (pinfunction "S_2") (pintype "input"))
      (node (ref "N24-2") (pin "2") (pinfunction "S_2") (pintype "input"))
      (node (ref "N25-2") (pin "2") (pinfunction "S_2") (pintype "input"))
      (node (ref "N26-2") (pin "2") (pinfunction "S_2") (pintype "input"))
      (node (ref "N27-2") (pin "2") (pinfunction "S_2") (pintype "input"))
      (node (ref "N28-2") (pin "2") (pinfunction "S_2") (pintype "input"))
      (node (ref "N29-2") (pin "2") (pinfunction "S_2") (pintype "input"))
      (node (ref "N3-2") (pin "2") (pinfunction "S_2") (pintype "input"))
      (node (ref "N30-2") (pin "2") (pinfunction "S_2") (pintype "input"))
      (node (ref "N4-2") (pin "2") (pinfunction "S_2") (pintype "input"))
      (node (ref "N5-2") (pin "2") (pinfunction "S_2") (pintype "input"))
      (node (ref "N6-2") (pin "2") (pinfunction "S_2") (pintype "input"))
      (node (ref "N7-2") (pin "2") (pinfunction "S_2") (pintype "input"))
      (node (ref "N8-2") (pin "2") (pinfunction "S_2") (pintype "input"))
      (node (ref "N9-2") (pin "2") (pinfunction "S_2") (pintype "input"))
      (node (ref "U1") (pin "10") (pinfunction "VSS_10") (pintype "input"))
      (node (ref "U1") (pin "11") (pinfunction "OD_11") (pintype "input"))
      (node (ref "U1") (pin "7") (pinfunction "TOG_7") (pintype "input"))
      (node (ref "U1") (pin "8") (pinfunction "LPMB_8") (pintype "input"))
      (node (ref "U1") (pin "9") (pinfunction "MOT0_9") (pintype "input"))
      (node (ref "U2") (pin "3") (pinfunction "COM_3") (pintype "unspecified"))
      (node (ref "U2") (pin "8") (pinfunction "COM_8") (pintype "unspecified"))
    )
    (net (code "2") (name "IN1") (class "Default")
      (node (ref "N1-1") (pin "1") (pinfunction "G_1") (pintype "input"))
      (node (ref "N1-2") (pin "1") (pinfunction "G_1") (pintype "input"))
      (node (ref "N2-1") (pin "1") (pinfunction "G_1") (pintype "input"))
      (node (ref "P1-1") (pin "1") (pinfunction "G_1") (pintype "input"))
      (node (ref "P1-2") (pin "1") (pinfunction "G_1") (pintype "input"))
      (node (ref "P2-1") (pin "1") (pinfunction "G_1") (pintype "input"))
      (node (ref "R1") (pin "1") (pinfunction "1_1") (pintype "input"))
      (node (ref "U1") (pin "16") (pinfunction "TPQ0_16") (pintype "input"))
    )
    (net (code "3") (name "IN2") (class "Default")
      (node (ref "N4-1") (pin "1") (pinfunction "G_1") (pintype "input"))
      (node (ref "N6-1") (pin "1") (pinfunction "G_1") (pintype "input"))
      (node (ref "P4-1") (pin "1") (pinfunction "G_1") (pintype "input"))
      (node (ref "P6-1") (pin "1") (pinfunction "G_1") (pintype "input"))
      (node (ref "R2") (pin "1") (pinfunction "1_1") (pintype "input"))
      (node (ref "U1") (pin "15") (pinfunction "TPQ1_15") (pintype "input"))
    )
    (net (code "4") (name "IN3") (class "Default")
      (node (ref "N2-2") (pin "1") (pinfunction "G_1") (pintype "input"))
      (node (ref "N9-2") (pin "1") (pinfunction "G_1") (pintype "input"))
      (node (ref "P2-2") (pin "1") (pinfunction "G_1") (pintype "input"))
      (node (ref "P9-2") (pin "1") (pinfunction "G_1") (pintype "input"))
      (node (ref "R3") (pin "1") (pinfunction "1_1") (pintype "input"))
      (node (ref "U1") (pin "14") (pinfunction "TPQ2_14") (pintype "input"))
    )
    (net (code "5") (name "IN4") (class "Default")
      (node (ref "N10-2") (pin "1") (pinfunction "G_1") (pintype "input"))
      (node (ref "N11-2") (pin "1") (pinfunction "G_1") (pintype "input"))
      (node (ref "N12-2") (pin "1") (pinfunction "G_1") (pintype "input"))
      (node (ref "N25-2") (pin "1") (pinfunction "G_1") (pintype "input"))
      (node (ref "N3-2") (pin "1") (pinfunction "G_1") (pintype "input"))
      (node (ref "P10-2") (pin "1") (pinfunction "G_1") (pintype "input"))
      (node (ref "P11-2") (pin "1") (pinfunction "G_1") (pintype "input"))
      (node (ref "P12-2") (pin "1") (pinfunction "G_1") (pintype "input"))
      (node (ref "P25-2") (pin "1") (pinfunction "G_1") (pintype "input"))
      (node (ref "P3-2") (pin "1") (pinfunction "G_1") (pintype "input"))
      (node (ref "R4") (pin "1") (pinfunction "1_1") (pintype "input"))
      (node (ref "U1") (pin "13") (pinfunction "TPQ3_13") (pintype "input"))
    )
    (net (code "6") (name "Net-(LED1-A)") (class "Default")
      (node (ref "LED1") (pin "2") (pinfunction "A_2") (pintype "input"))
      (node (ref "R1") (pin "2") (pinfunction "2_2") (pintype "input"))
    )
    (net (code "7") (name "Net-(LED2-A)") (class "Default")
      (node (ref "LED2") (pin "2") (pinfunction "A_2") (pintype "input"))
      (node (ref "R2") (pin "2") (pinfunction "2_2") (pintype "input"))
    )
    (net (code "8") (name "Net-(LED3-A)") (class "Default")
      (node (ref "LED3") (pin "2") (pinfunction "A_2") (pintype "input"))
      (node (ref "R3") (pin "2") (pinfunction "2_2") (pintype "input"))
    )
    (net (code "9") (name "Net-(LED4-A)") (class "Default")
      (node (ref "LED4") (pin "2") (pinfunction "A_2") (pintype "input"))
      (node (ref "R4") (pin "2") (pinfunction "2_2") (pintype "input"))
    )
    (net (code "10") (name "Net-(N1-1-S)") (class "Default")
      (node (ref "N1-1") (pin "2") (pinfunction "S_2") (pintype "input"))
      (node (ref "N1-2") (pin "3") (pinfunction "D_3") (pintype "input"))
    )
    (net (code "11") (name "Net-(N2-1-S)") (class "Default")
      (node (ref "N2-1") (pin "2") (pinfunction "S_2") (pintype "input"))
      (node (ref "N2-2") (pin "3") (pinfunction "D_3") (pintype "input"))
    )
    (net (code "12") (name "Net-(N3-1-S)") (class "Default")
      (node (ref "N3-1") (pin "2") (pinfunction "S_2") (pintype "input"))
      (node (ref "N3-2") (pin "3") (pinfunction "D_3") (pintype "input"))
    )
    (net (code "13") (name "Net-(N4-1-S)") (class "Default")
      (node (ref "N4-1") (pin "2") (pinfunction "S_2") (pintype "input"))
      (node (ref "N4-2") (pin "3") (pinfunction "D_3") (pintype "input"))
    )
    (net (code "14") (name "Net-(N5-1-S)") (class "Default")
      (node (ref "N5-1") (pin "2") (pinfunction "S_2") (pintype "input"))
      (node (ref "N5-2") (pin "3") (pinfunction "D_3") (pintype "input"))
    )
    (net (code "15") (name "Net-(N6-1-S)") (class "Default")
      (node (ref "N6-1") (pin "2") (pinfunction "S_2") (pintype "input"))
      (node (ref "N6-2") (pin "3") (pinfunction "D_3") (pintype "input"))
    )
    (net (code "16") (name "Net-(N7-1-S)") (class "Default")
      (node (ref "N7-1") (pin "2") (pinfunction "S_2") (pintype "input"))
      (node (ref "N7-2") (pin "3") (pinfunction "D_3") (pintype "input"))
    )
    (net (code "17") (name "Net-(N8-1-S)") (class "Default")
      (node (ref "N8-1") (pin "2") (pinfunction "S_2") (pintype "input"))
      (node (ref "N8-2") (pin "3") (pinfunction "D_3") (pintype "input"))
    )
    (net (code "18") (name "Net-(N9-1-S)") (class "Default")
      (node (ref "N9-1") (pin "2") (pinfunction "S_2") (pintype "input"))
      (node (ref "N9-2") (pin "3") (pinfunction "D_3") (pintype "input"))
    )
    (net (code "19") (name "Net-(N10-1-S)") (class "Default")
      (node (ref "N10-1") (pin "2") (pinfunction "S_2") (pintype "input"))
      (node (ref "N10-2") (pin "3") (pinfunction "D_3") (pintype "input"))
    )
    (net (code "20") (name "Net-(N11-1-S)") (class "Default")
      (node (ref "N11-1") (pin "2") (pinfunction "S_2") (pintype "input"))
      (node (ref "N11-2") (pin "3") (pinfunction "D_3") (pintype "input"))
    )
    (net (code "21") (name "Net-(N12-1-S)") (class "Default")
      (node (ref "N12-1") (pin "2") (pinfunction "S_2") (pintype "input"))
      (node (ref "N12-2") (pin "3") (pinfunction "D_3") (pintype "input"))
    )
    (net (code "22") (name "Net-(N13-1-S)") (class "Default")
      (node (ref "N13-1") (pin "2") (pinfunction "S_2") (pintype "input"))
      (node (ref "N13-2") (pin "3") (pinfunction "D_3") (pintype "input"))
    )
    (net (code "23") (name "Net-(N14-1-S)") (class "Default")
      (node (ref "N14-1") (pin "2") (pinfunction "S_2") (pintype "input"))
      (node (ref "N14-2") (pin "3") (pinfunction "D_3") (pintype "input"))
    )
    (net (code "24") (name "Net-(N15-1-S)") (class "Default")
      (node (ref "N15-1") (pin "2") (pinfunction "S_2") (pintype "input"))
      (node (ref "N15-2") (pin "3") (pinfunction "D_3") (pintype "input"))
    )
    (net (code "25") (name "Net-(N16-1-S)") (class "Default")
      (node (ref "N16-1") (pin "2") (pinfunction "S_2") (pintype "input"))
      (node (ref "N16-2") (pin "3") (pinfunction "D_3") (pintype "input"))
    )
    (net (code "26") (name "Net-(N17-1-S)") (class "Default")
      (node (ref "N17-1") (pin "2") (pinfunction "S_2") (pintype "input"))
      (node (ref "N17-2") (pin "3") (pinfunction "D_3") (pintype "input"))
    )
    (net (code "27") (name "Net-(N18-1-S)") (class "Default")
      (node (ref "N18-1") (pin "2") (pinfunction "S_2") (pintype "input"))
      (node (ref "N18-2") (pin "3") (pinfunction "D_3") (pintype "input"))
    )
    (net (code "28") (name "Net-(N19-1-S)") (class "Default")
      (node (ref "N19-1") (pin "2") (pinfunction "S_2") (pintype "input"))
      (node (ref "N19-2") (pin "3") (pinfunction "D_3") (pintype "input"))
    )
    (net (code "29") (name "Net-(N20-1-S)") (class "Default")
      (node (ref "N20-1") (pin "2") (pinfunction "S_2") (pintype "input"))
      (node (ref "N20-2") (pin "3") (pinfunction "D_3") (pintype "input"))
    )
    (net (code "30") (name "Net-(N21-1-S)") (class "Default")
      (node (ref "N21-1") (pin "2") (pinfunction "S_2") (pintype "input"))
      (node (ref "N21-2") (pin "3") (pinfunction "D_3") (pintype "input"))
    )
    (net (code "31") (name "Net-(N22-1-S)") (class "Default")
      (node (ref "N22-1") (pin "2") (pinfunction "S_2") (pintype "input"))
      (node (ref "N22-2") (pin "3") (pinfunction "D_3") (pintype "input"))
    )
    (net (code "32") (name "Net-(N23-1-S)") (class "Default")
      (node (ref "N23-1") (pin "2") (pinfunction "S_2") (pintype "input"))
      (node (ref "N23-2") (pin "3") (pinfunction "D_3") (pintype "input"))
    )
    (net (code "33") (name "Net-(N24-1-S)") (class "Default")
      (node (ref "N24-1") (pin "2") (pinfunction "S_2") (pintype "input"))
      (node (ref "N24-2") (pin "3") (pinfunction "D_3") (pintype "input"))
    )
    (net (code "34") (name "Net-(N25-1-S)") (class "Default")
      (node (ref "N25-1") (pin "2") (pinfunction "S_2") (pintype "input"))
      (node (ref "N25-2") (pin "3") (pinfunction "D_3") (pintype "input"))
    )
    (net (code "35") (name "Net-(N26-1-S)") (class "Default")
      (node (ref "N26-1") (pin "2") (pinfunction "S_2") (pintype "input"))
      (node (ref "N26-2") (pin "3") (pinfunction "D_3") (pintype "input"))
    )
    (net (code "36") (name "Net-(N27-1-S)") (class "Default")
      (node (ref "N27-1") (pin "2") (pinfunction "S_2") (pintype "input"))
      (node (ref "N27-2") (pin "3") (pinfunction "D_3") (pintype "input"))
    )
    (net (code "37") (name "Net-(N28-1-S)") (class "Default")
      (node (ref "N28-1") (pin "2") (pinfunction "S_2") (pintype "input"))
      (node (ref "N28-2") (pin "3") (pinfunction "D_3") (pintype "input"))
    )
    (net (code "38") (name "Net-(N29-1-S)") (class "Default")
      (node (ref "N29-1") (pin "2") (pinfunction "S_2") (pintype "input"))
      (node (ref "N29-2") (pin "3") (pinfunction "D_3") (pintype "input"))
    )
    (net (code "39") (name "Net-(N30-1-S)") (class "Default")
      (node (ref "N30-1") (pin "2") (pinfunction "S_2") (pintype "input"))
      (node (ref "N30-2") (pin "3") (pinfunction "D_3") (pintype "input"))
    )
    (net (code "40") (name "Net-(U2-A)") (class "Default")
      (node (ref "R11") (pin "1") (pinfunction "1_1") (pintype "input"))
      (node (ref "U2") (pin "7") (pinfunction "A_7") (pintype "unspecified"))
    )
    (net (code "41") (name "Net-(U2-B)") (class "Default")
      (node (ref "R10") (pin "1") (pinfunction "1_1") (pintype "input"))
      (node (ref "U2") (pin "6") (pinfunction "B_6") (pintype "unspecified"))
    )
    (net (code "42") (name "Net-(U2-C)") (class "Default")
      (node (ref "R8") (pin "2") (pinfunction "2_2") (pintype "input"))
      (node (ref "U2") (pin "4") (pinfunction "C_4") (pintype "unspecified"))
    )
    (net (code "43") (name "Net-(U2-D)") (class "Default")
      (node (ref "R6") (pin "2") (pinfunction "2_2") (pintype "input"))
      (node (ref "U2") (pin "2") (pinfunction "D_2") (pintype "unspecified"))
    )
    (net (code "44") (name "Net-(U2-DP)") (class "Default")
      (node (ref "R9") (pin "2") (pinfunction "2_2") (pintype "input"))
      (node (ref "U2") (pin "5") (pinfunction "DP_5") (pintype "unspecified"))
    )
    (net (code "45") (name "Net-(U2-E)") (class "Default")
      (node (ref "R5") (pin "2") (pinfunction "2_2") (pintype "input"))
      (node (ref "U2") (pin "1") (pinfunction "E_1") (pintype "unspecified"))
    )
    (net (code "46") (name "Net-(U2-F)") (class "Default")
      (node (ref "R13") (pin "1") (pinfunction "1_1") (pintype "input"))
      (node (ref "U2") (pin "9") (pinfunction "F_9") (pintype "unspecified"))
    )
    (net (code "47") (name "Net-(U2-G)") (class "Default")
      (node (ref "R14") (pin "1") (pinfunction "1_1") (pintype "input"))
      (node (ref "U2") (pin "10") (pinfunction "G_10") (pintype "unspecified"))
    )
    (net (code "48") (name "OUT-1-1") (class "Default")
      (node (ref "N1-1") (pin "3") (pinfunction "D_3") (pintype "input"))
      (node (ref "N16-1") (pin "1") (pinfunction "G_1") (pintype "input"))
      (node (ref "N26-1") (pin "1") (pinfunction "G_1") (pintype "input"))
      (node (ref "N3-1") (pin "1") (pinfunction "G_1") (pintype "input"))
      (node (ref "P1-1") (pin "3") (pinfunction "D_3") (pintype "input"))
      (node (ref "P1-2") (pin "3") (pinfunction "D_3") (pintype "input"))
      (node (ref "P16-1") (pin "1") (pinfunction "G_1") (pintype "input"))
      (node (ref "P26-1") (pin "1") (pinfunction "G_1") (pintype "input"))
      (node (ref "P3-1") (pin "1") (pinfunction "G_1") (pintype "input"))
    )
    (net (code "49") (name "OUT-1-2") (class "Default")
      (node (ref "N2-1") (pin "3") (pinfunction "D_3") (pintype "input"))
      (node (ref "N4-2") (pin "1") (pinfunction "G_1") (pintype "input"))
      (node (ref "N5-1") (pin "1") (pinfunction "G_1") (pintype "input"))
      (node (ref "P2-1") (pin "3") (pinfunction "D_3") (pintype "input"))
      (node (ref "P2-2") (pin "3") (pinfunction "D_3") (pintype "input"))
      (node (ref "P4-2") (pin "1") (pinfunction "G_1") (pintype "input"))
      (node (ref "P5-1") (pin "1") (pinfunction "G_1") (pintype "input"))
    )
    (net (code "50") (name "OUT-2-1") (class "Default")
      (node (ref "N3-1") (pin "3") (pinfunction "D_3") (pintype "input"))
      (node (ref "N7-1") (pin "1") (pinfunction "G_1") (pintype "input"))
      (node (ref "P3-1") (pin "3") (pinfunction "D_3") (pintype "input"))
      (node (ref "P3-2") (pin "3") (pinfunction "D_3") (pintype "input"))
      (node (ref "P7-1") (pin "1") (pinfunction "G_1") (pintype "input"))
    )
    (net (code "51") (name "OUT-2-2") (class "Default")
      (node (ref "N4-1") (pin "3") (pinfunction "D_3") (pintype "input"))
      (node (ref "N5-2") (pin "1") (pinfunction "G_1") (pintype "input"))
      (node (ref "N6-2") (pin "1") (pinfunction "G_1") (pintype "input"))
      (node (ref "P4-1") (pin "3") (pinfunction "D_3") (pintype "input"))
      (node (ref "P4-2") (pin "3") (pinfunction "D_3") (pintype "input"))
      (node (ref "P5-2") (pin "1") (pinfunction "G_1") (pintype "input"))
      (node (ref "P6-2") (pin "1") (pinfunction "G_1") (pintype "input"))
    )
    (net (code "52") (name "OUT-3-1") (class "Default")
      (node (ref "N20-1") (pin "1") (pinfunction "G_1") (pintype "input"))
      (node (ref "N5-1") (pin "3") (pinfunction "D_3") (pintype "input"))
      (node (ref "N7-2") (pin "1") (pinfunction "G_1") (pintype "input"))
      (node (ref "N8-1") (pin "1") (pinfunction "G_1") (pintype "input"))
      (node (ref "P20-1") (pin "1") (pinfunction "G_1") (pintype "input"))
      (node (ref "P5-1") (pin "3") (pinfunction "D_3") (pintype "input"))
      (node (ref "P5-2") (pin "3") (pinfunction "D_3") (pintype "input"))
      (node (ref "P7-2") (pin "1") (pinfunction "G_1") (pintype "input"))
      (node (ref "P8-1") (pin "1") (pinfunction "G_1") (pintype "input"))
    )
    (net (code "53") (name "OUT-3-2") (class "Default")
      (node (ref "N18-2") (pin "1") (pinfunction "G_1") (pintype "input"))
      (node (ref "N6-1") (pin "3") (pinfunction "D_3") (pintype "input"))
      (node (ref "N8-2") (pin "1") (pinfunction "G_1") (pintype "input"))
      (node (ref "N9-1") (pin "1") (pinfunction "G_1") (pintype "input"))
      (node (ref "P18-2") (pin "1") (pinfunction "G_1") (pintype "input"))
      (node (ref "P6-1") (pin "3") (pinfunction "D_3") (pintype "input"))
      (node (ref "P6-2") (pin "3") (pinfunction "D_3") (pintype "input"))
      (node (ref "P8-2") (pin "1") (pinfunction "G_1") (pintype "input"))
      (node (ref "P9-1") (pin "1") (pinfunction "G_1") (pintype "input"))
    )
    (net (code "54") (name "OUT-4-1") (class "Default")
      (node (ref "N14-1") (pin "1") (pinfunction "G_1") (pintype "input"))
      (node (ref "N22-2") (pin "1") (pinfunction "G_1") (pintype "input"))
      (node (ref "N7-1") (pin "3") (pinfunction "D_3") (pintype "input"))
      (node (ref "P14-1") (pin "1") (pinfunction "G_1") (pintype "input"))
      (node (ref "P22-2") (pin "1") (pinfunction "G_1") (pintype "input"))
      (node (ref "P7-1") (pin "3") (pinfunction "D_3") (pintype "input"))
      (node (ref "P7-2") (pin "3") (pinfunction "D_3") (pintype "input"))
    )
    (net (code "55") (name "OUT-4-2") (class "Default")
      (node (ref "N10-1") (pin "1") (pinfunction "G_1") (pintype "input"))
      (node (ref "N17-1") (pin "1") (pinfunction "G_1") (pintype "input"))
      (node (ref "N8-1") (pin "3") (pinfunction "D_3") (pintype "input"))
      (node (ref "P10-1") (pin "1") (pinfunction "G_1") (pintype "input"))
      (node (ref "P17-1") (pin "1") (pinfunction "G_1") (pintype "input"))
      (node (ref "P8-1") (pin "3") (pinfunction "D_3") (pintype "input"))
      (node (ref "P8-2") (pin "3") (pinfunction "D_3") (pintype "input"))
    )
    (net (code "56") (name "OUT-4-3") (class "Default")
      (node (ref "N11-1") (pin "1") (pinfunction "G_1") (pintype "input"))
      (node (ref "N13-2") (pin "1") (pinfunction "G_1") (pintype "input"))
      (node (ref "N9-1") (pin "3") (pinfunction "D_3") (pintype "input"))
      (node (ref "P11-1") (pin "1") (pinfunction "G_1") (pintype "input"))
      (node (ref "P13-2") (pin "1") (pinfunction "G_1") (pintype "input"))
      (node (ref "P9-1") (pin "3") (pinfunction "D_3") (pintype "input"))
      (node (ref "P9-2") (pin "3") (pinfunction "D_3") (pintype "input"))
    )
    (net (code "57") (name "OUT-5-1") (class "Default")
      (node (ref "N10-1") (pin "3") (pinfunction "D_3") (pintype "input"))
      (node (ref "N19-2") (pin "1") (pinfunction "G_1") (pintype "input"))
      (node (ref "P10-1") (pin "3") (pinfunction "D_3") (pintype "input"))
      (node (ref "P10-2") (pin "3") (pinfunction "D_3") (pintype "input"))
      (node (ref "P19-2") (pin "1") (pinfunction "G_1") (pintype "input"))
    )
    (net (code "58") (name "OUT-5-2") (class "Default")
      (node (ref "N11-1") (pin "3") (pinfunction "D_3") (pintype "input"))
      (node (ref "N12-1") (pin "1") (pinfunction "G_1") (pintype "input"))
      (node (ref "N13-1") (pin "1") (pinfunction "G_1") (pintype "input"))
      (node (ref "P11-1") (pin "3") (pinfunction "D_3") (pintype "input"))
      (node (ref "P11-2") (pin "3") (pinfunction "D_3") (pintype "input"))
      (node (ref "P12-1") (pin "1") (pinfunction "G_1") (pintype "input"))
      (node (ref "P13-1") (pin "1") (pinfunction "G_1") (pintype "input"))
    )
    (net (code "59") (name "OUT-6-1") (class "Default")
      (node (ref "N12-1") (pin "3") (pinfunction "D_3") (pintype "input"))
      (node (ref "N14-2") (pin "1") (pinfunction "G_1") (pintype "input"))
      (node (ref "N15-2") (pin "1") (pinfunction "G_1") (pintype "input"))
      (node (ref "P12-1") (pin "3") (pinfunction "D_3") (pintype "input"))
      (node (ref "P12-2") (pin "3") (pinfunction "D_3") (pintype "input"))
      (node (ref "P14-2") (pin "1") (pinfunction "G_1") (pintype "input"))
      (node (ref "P15-2") (pin "1") (pinfunction "G_1") (pintype "input"))
    )
    (net (code "60") (name "OUT-6-2") (class "Default")
      (node (ref "N13-1") (pin "3") (pinfunction "D_3") (pintype "input"))
      (node (ref "N15-1") (pin "1") (pinfunction "G_1") (pintype "input"))
      (node (ref "P13-1") (pin "3") (pinfunction "D_3") (pintype "input"))
      (node (ref "P13-2") (pin "3") (pinfunction "D_3") (pintype "input"))
      (node (ref "P15-1") (pin "1") (pinfunction "G_1") (pintype "input"))
    )
    (net (code "61") (name "OUT-7-1") (class "Default")
      (node (ref "N14-1") (pin "3") (pinfunction "D_3") (pintype "input"))
      (node (ref "N18-1") (pin "1") (pinfunction "G_1") (pintype "input"))
      (node (ref "N21-2") (pin "1") (pinfunction "G_1") (pintype "input"))
      (node (ref "N27-1") (pin "1") (pinfunction "G_1") (pintype "input"))
      (node (ref "P14-1") (pin "3") (pinfunction "D_3") (pintype "input"))
      (node (ref "P14-2") (pin "3") (pinfunction "D_3") (pintype "input"))
      (node (ref "P18-1") (pin "1") (pinfunction "G_1") (pintype "input"))
      (node (ref "P21-2") (pin "1") (pinfunction "G_1") (pintype "input"))
      (node (ref "P27-1") (pin "1") (pinfunction "G_1") (pintype "input"))
    )
    (net (code "62") (name "OUT-7-2") (class "Default")
      (node (ref "N15-1") (pin "3") (pinfunction "D_3") (pintype "input"))
      (node (ref "N16-2") (pin "1") (pinfunction "G_1") (pintype "input"))
      (node (ref "N17-2") (pin "1") (pinfunction "G_1") (pintype "input"))
      (node (ref "N23-2") (pin "1") (pinfunction "G_1") (pintype "input"))
      (node (ref "P15-1") (pin "3") (pinfunction "D_3") (pintype "input"))
      (node (ref "P15-2") (pin "3") (pinfunction "D_3") (pintype "input"))
      (node (ref "P16-2") (pin "1") (pinfunction "G_1") (pintype "input"))
      (node (ref "P17-2") (pin "1") (pinfunction "G_1") (pintype "input"))
      (node (ref "P23-2") (pin "1") (pinfunction "G_1") (pintype "input"))
    )
    (net (code "63") (name "OUT-8-1") (class "Default")
      (node (ref "N16-1") (pin "3") (pinfunction "D_3") (pintype "input"))
      (node (ref "N19-1") (pin "1") (pinfunction "G_1") (pintype "input"))
      (node (ref "P16-1") (pin "3") (pinfunction "D_3") (pintype "input"))
      (node (ref "P16-2") (pin "3") (pinfunction "D_3") (pintype "input"))
      (node (ref "P19-1") (pin "1") (pinfunction "G_1") (pintype "input"))
    )
    (net (code "64") (name "OUT-8-2") (class "Default")
      (node (ref "N17-1") (pin "3") (pinfunction "D_3") (pintype "input"))
      (node (ref "P17-1") (pin "3") (pinfunction "D_3") (pintype "input"))
      (node (ref "P17-2") (pin "3") (pinfunction "D_3") (pintype "input"))
      (node (ref "R14") (pin "2") (pinfunction "2_2") (pintype "input"))
    )
    (net (code "65") (name "OUT-8-3") (class "Default")
      (node (ref "N18-1") (pin "3") (pinfunction "D_3") (pintype "input"))
      (node (ref "N20-2") (pin "1") (pinfunction "G_1") (pintype "input"))
      (node (ref "N24-2") (pin "1") (pinfunction "G_1") (pintype "input"))
      (node (ref "P18-1") (pin "3") (pinfunction "D_3") (pintype "input"))
      (node (ref "P18-2") (pin "3") (pinfunction "D_3") (pintype "input"))
      (node (ref "P20-2") (pin "1") (pinfunction "G_1") (pintype "input"))
      (node (ref "P24-2") (pin "1") (pinfunction "G_1") (pintype "input"))
    )
    (net (code "66") (name "OUT-9-1") (class "Default")
      (node (ref "N19-1") (pin "3") (pinfunction "D_3") (pintype "input"))
      (node (ref "N21-1") (pin "1") (pinfunction "G_1") (pintype "input"))
      (node (ref "N22-1") (pin "1") (pinfunction "G_1") (pintype "input"))
      (node (ref "P19-1") (pin "3") (pinfunction "D_3") (pintype "input"))
      (node (ref "P19-2") (pin "3") (pinfunction "D_3") (pintype "input"))
      (node (ref "P21-1") (pin "1") (pinfunction "G_1") (pintype "input"))
      (node (ref "P22-1") (pin "1") (pinfunction "G_1") (pintype "input"))
    )
    (net (code "67") (name "OUT-9-2") (class "Default")
      (node (ref "N20-1") (pin "3") (pinfunction "D_3") (pintype "input"))
      (node (ref "N30-1") (pin "1") (pinfunction "G_1") (pintype "input"))
      (node (ref "P20-1") (pin "3") (pinfunction "D_3") (pintype "input"))
      (node (ref "P20-2") (pin "3") (pinfunction "D_3") (pintype "input"))
      (node (ref "P30-1") (pin "1") (pinfunction "G_1") (pintype "input"))
    )
    (net (code "68") (name "OUT-10-1") (class "Default")
      (node (ref "N21-1") (pin "3") (pinfunction "D_3") (pintype "input"))
      (node (ref "P21-1") (pin "3") (pinfunction "D_3") (pintype "input"))
      (node (ref "P21-2") (pin "3") (pinfunction "D_3") (pintype "input"))
      (node (ref "R8") (pin "1") (pinfunction "1_1") (pintype "input"))
    )
    (net (code "69") (name "OUT-10-2") (class "Default")
      (node (ref "N22-1") (pin "3") (pinfunction "D_3") (pintype "input"))
      (node (ref "N23-1") (pin "1") (pinfunction "G_1") (pintype "input"))
      (node (ref "N24-1") (pin "1") (pinfunction "G_1") (pintype "input"))
      (node (ref "N25-1") (pin "1") (pinfunction "G_1") (pintype "input"))
      (node (ref "P22-1") (pin "3") (pinfunction "D_3") (pintype "input"))
      (node (ref "P22-2") (pin "3") (pinfunction "D_3") (pintype "input"))
      (node (ref "P23-1") (pin "1") (pinfunction "G_1") (pintype "input"))
      (node (ref "P24-1") (pin "1") (pinfunction "G_1") (pintype "input"))
      (node (ref "P25-1") (pin "1") (pinfunction "G_1") (pintype "input"))
    )
    (net (code "70") (name "OUT-11-1") (class "Default")
      (node (ref "N23-1") (pin "3") (pinfunction "D_3") (pintype "input"))
      (node (ref "N27-2") (pin "1") (pinfunction "G_1") (pintype "input"))
      (node (ref "P23-1") (pin "3") (pinfunction "D_3") (pintype "input"))
      (node (ref "P23-2") (pin "3") (pinfunction "D_3") (pintype "input"))
      (node (ref "P27-2") (pin "1") (pinfunction "G_1") (pintype "input"))
      (node (ref "R13") (pin "2") (pinfunction "2_2") (pintype "input"))
    )
    (net (code "71") (name "OUT-11-2") (class "Default")
      (node (ref "N24-1") (pin "3") (pinfunction "D_3") (pintype "input"))
      (node (ref "N26-2") (pin "1") (pinfunction "G_1") (pintype "input"))
      (node (ref "N28-1") (pin "1") (pinfunction "G_1") (pintype "input"))
      (node (ref "P24-1") (pin "3") (pinfunction "D_3") (pintype "input"))
      (node (ref "P24-2") (pin "3") (pinfunction "D_3") (pintype "input"))
      (node (ref "P26-2") (pin "1") (pinfunction "G_1") (pintype "input"))
      (node (ref "P28-1") (pin "1") (pinfunction "G_1") (pintype "input"))
      (node (ref "R6") (pin "1") (pinfunction "1_1") (pintype "input"))
    )
    (net (code "72") (name "OUT-11-3") (class "Default")
      (node (ref "N25-1") (pin "3") (pinfunction "D_3") (pintype "input"))
      (node (ref "N28-2") (pin "1") (pinfunction "G_1") (pintype "input"))
      (node (ref "N29-2") (pin "1") (pinfunction "G_1") (pintype "input"))
      (node (ref "P25-1") (pin "3") (pinfunction "D_3") (pintype "input"))
      (node (ref "P25-2") (pin "3") (pinfunction "D_3") (pintype "input"))
      (node (ref "P28-2") (pin "1") (pinfunction "G_1") (pintype "input"))
      (node (ref "P29-2") (pin "1") (pinfunction "G_1") (pintype "input"))
    )
    (net (code "73") (name "OUT-12-1") (class "Default")
      (node (ref "N26-1") (pin "3") (pinfunction "D_3") (pintype "input"))
      (node (ref "N29-1") (pin "1") (pinfunction "G_1") (pintype "input"))
      (node (ref "P26-1") (pin "3") (pinfunction "D_3") (pintype "input"))
      (node (ref "P26-2") (pin "3") (pinfunction "D_3") (pintype "input"))
      (node (ref "P29-1") (pin "1") (pinfunction "G_1") (pintype "input"))
    )
    (net (code "74") (name "OUT-12-2") (class "Default")
      (node (ref "N27-1") (pin "3") (pinfunction "D_3") (pintype "input"))
      (node (ref "P27-1") (pin "3") (pinfunction "D_3") (pintype "input"))
      (node (ref "P27-2") (pin "3") (pinfunction "D_3") (pintype "input"))
      (node (ref "R10") (pin "2") (pinfunction "2_2") (pintype "input"))
    )
    (net (code "75") (name "OUT-12-3") (class "Default")
      (node (ref "N28-1") (pin "3") (pinfunction "D_3") (pintype "input"))
      (node (ref "N30-2") (pin "1") (pinfunction "G_1") (pintype "input"))
      (node (ref "P28-1") (pin "3") (pinfunction "D_3") (pintype "input"))
      (node (ref "P28-2") (pin "3") (pinfunction "D_3") (pintype "input"))
      (node (ref "P30-2") (pin "1") (pinfunction "G_1") (pintype "input"))
    )
    (net (code "76") (name "OUT-13-1") (class "Default")
      (node (ref "N29-1") (pin "3") (pinfunction "D_3") (pintype "input"))
      (node (ref "P29-1") (pin "3") (pinfunction "D_3") (pintype "input"))
      (node (ref "P29-2") (pin "3") (pinfunction "D_3") (pintype "input"))
      (node (ref "R5") (pin "1") (pinfunction "1_1") (pintype "input"))
    )
    (net (code "77") (name "OUT-13-2") (class "Default")
      (node (ref "N30-1") (pin "3") (pinfunction "D_3") (pintype "input"))
      (node (ref "P30-1") (pin "3") (pinfunction "D_3") (pintype "input"))
      (node (ref "P30-2") (pin "3") (pinfunction "D_3") (pintype "input"))
      (node (ref "R11") (pin "2") (pinfunction "2_2") (pintype "input"))
    )
    (net (code "78") (name "TP1") (class "Default")
      (node (ref "U1") (pin "1") (pinfunction "TP0_1") (pintype "input"))
    )
    (net (code "79") (name "TP2") (class "Default")
      (node (ref "U1") (pin "2") (pinfunction "TP1_2") (pintype "input"))
    )
    (net (code "80") (name "TP3") (class "Default")
      (node (ref "U1") (pin "3") (pinfunction "TP2_3") (pintype "input"))
    )
    (net (code "81") (name "TP4") (class "Default")
      (node (ref "U1") (pin "4") (pinfunction "TP3_4") (pintype "input"))
    )
    (net (code "82") (name "VCC") (class "Default")
      (node (ref "C1") (pin "1") (pinfunction "1_1") (pintype "input"))
      (node (ref "P1-1") (pin "2") (pinfunction "S_2") (pintype "input"))
      (node (ref "P1-2") (pin "2") (pinfunction "S_2") (pintype "input"))
      (node (ref "P10-1") (pin "2") (pinfunction "S_2") (pintype "input"))
      (node (ref "P10-2") (pin "2") (pinfunction "S_2") (pintype "input"))
      (node (ref "P11-1") (pin "2") (pinfunction "S_2") (pintype "input"))
      (node (ref "P11-2") (pin "2") (pinfunction "S_2") (pintype "input"))
      (node (ref "P12-1") (pin "2") (pinfunction "S_2") (pintype "input"))
      (node (ref "P12-2") (pin "2") (pinfunction "S_2") (pintype "input"))
      (node (ref "P13-1") (pin "2") (pinfunction "S_2") (pintype "input"))
      (node (ref "P13-2") (pin "2") (pinfunction "S_2") (pintype "input"))
      (node (ref "P14-1") (pin "2") (pinfunction "S_2") (pintype "input"))
      (node (ref "P14-2") (pin "2") (pinfunction "S_2") (pintype "input"))
      (node (ref "P15-1") (pin "2") (pinfunction "S_2") (pintype "input"))
      (node (ref "P15-2") (pin "2") (pinfunction "S_2") (pintype "input"))
      (node (ref "P16-1") (pin "2") (pinfunction "S_2") (pintype "input"))
      (node (ref "P16-2") (pin "2") (pinfunction "S_2") (pintype "input"))
      (node (ref "P17-1") (pin "2") (pinfunction "S_2") (pintype "input"))
      (node (ref "P17-2") (pin "2") (pinfunction "S_2") (pintype "input"))
      (node (ref "P18-1") (pin "2") (pinfunction "S_2") (pintype "input"))
      (node (ref "P18-2") (pin "2") (pinfunction "S_2") (pintype "input"))
      (node (ref "P19-1") (pin "2") (pinfunction "S_2") (pintype "input"))
      (node (ref "P19-2") (pin "2") (pinfunction "S_2") (pintype "input"))
      (node (ref "P2-1") (pin "2") (pinfunction "S_2") (pintype "input"))
      (node (ref "P2-2") (pin "2") (pinfunction "S_2") (pintype "input"))
      (node (ref "P20-1") (pin "2") (pinfunction "S_2") (pintype "input"))
      (node (ref "P20-2") (pin "2") (pinfunction "S_2") (pintype "input"))
      (node (ref "P21-1") (pin "2") (pinfunction "S_2") (pintype "input"))
      (node (ref "P21-2") (pin "2") (pinfunction "S_2") (pintype "input"))
      (node (ref "P22-1") (pin "2") (pinfunction "S_2") (pintype "input"))
      (node (ref "P22-2") (pin "2") (pinfunction "S_2") (pintype "input"))
      (node (ref "P23-1") (pin "2") (pinfunction "S_2") (pintype "input"))
      (node (ref "P23-2") (pin "2") (pinfunction "S_2") (pintype "input"))
      (node (ref "P24-1") (pin "2") (pinfunction "S_2") (pintype "input"))
      (node (ref "P24-2") (pin "2") (pinfunction "S_2") (pintype "input"))
      (node (ref "P25-1") (pin "2") (pinfunction "S_2") (pintype "input"))
      (node (ref "P25-2") (pin "2") (pinfunction "S_2") (pintype "input"))
      (node (ref "P26-1") (pin "2") (pinfunction "S_2") (pintype "input"))
      (node (ref "P26-2") (pin "2") (pinfunction "S_2") (pintype "input"))
      (node (ref "P27-1") (pin "2") (pinfunction "S_2") (pintype "input"))
      (node (ref "P27-2") (pin "2") (pinfunction "S_2") (pintype "input"))
      (node (ref "P28-1") (pin "2") (pinfunction "S_2") (pintype "input"))
      (node (ref "P28-2") (pin "2") (pinfunction "S_2") (pintype "input"))
      (node (ref "P29-1") (pin "2") (pinfunction "S_2") (pintype "input"))
      (node (ref "P29-2") (pin "2") (pinfunction "S_2") (pintype "input"))
      (node (ref "P3-1") (pin "2") (pinfunction "S_2") (pintype "input"))
      (node (ref "P3-2") (pin "2") (pinfunction "S_2") (pintype "input"))
      (node (ref "P30-1") (pin "2") (pinfunction "S_2") (pintype "input"))
      (node (ref "P30-2") (pin "2") (pinfunction "S_2") (pintype "input"))
      (node (ref "P4-1") (pin "2") (pinfunction "S_2") (pintype "input"))
      (node (ref "P4-2") (pin "2") (pinfunction "S_2") (pintype "input"))
      (node (ref "P5-1") (pin "2") (pinfunction "S_2") (pintype "input"))
      (node (ref "P5-2") (pin "2") (pinfunction "S_2") (pintype "input"))
      (node (ref "P6-1") (pin "2") (pinfunction "S_2") (pintype "input"))
      (node (ref "P6-2") (pin "2") (pinfunction "S_2") (pintype "input"))
      (node (ref "P7-1") (pin "2") (pinfunction "S_2") (pintype "input"))
      (node (ref "P7-2") (pin "2") (pinfunction "S_2") (pintype "input"))
      (node (ref "P8-1") (pin "2") (pinfunction "S_2") (pintype "input"))
      (node (ref "P8-2") (pin "2") (pinfunction "S_2") (pintype "input"))
      (node (ref "P9-1") (pin "2") (pinfunction "S_2") (pintype "input"))
      (node (ref "P9-2") (pin "2") (pinfunction "S_2") (pintype "input"))
      (node (ref "R9") (pin "1") (pinfunction "1_1") (pintype "input"))
      (node (ref "U1") (pin "12") (pinfunction "SM_12") (pintype "input"))
      (node (ref "U1") (pin "5") (pinfunction "AHLB_5") (pintype "input"))
      (node (ref "U1") (pin "6") (pinfunction "VDD_6") (pintype "input"))
      (node (ref "VCC") (pin "1") (pinfunction "1_1") (pintype "unspecified"))
    )
  )
)
